# adc-circit-ADS7952.net
KiCad netlist of a schematic drawn in Altium Designer
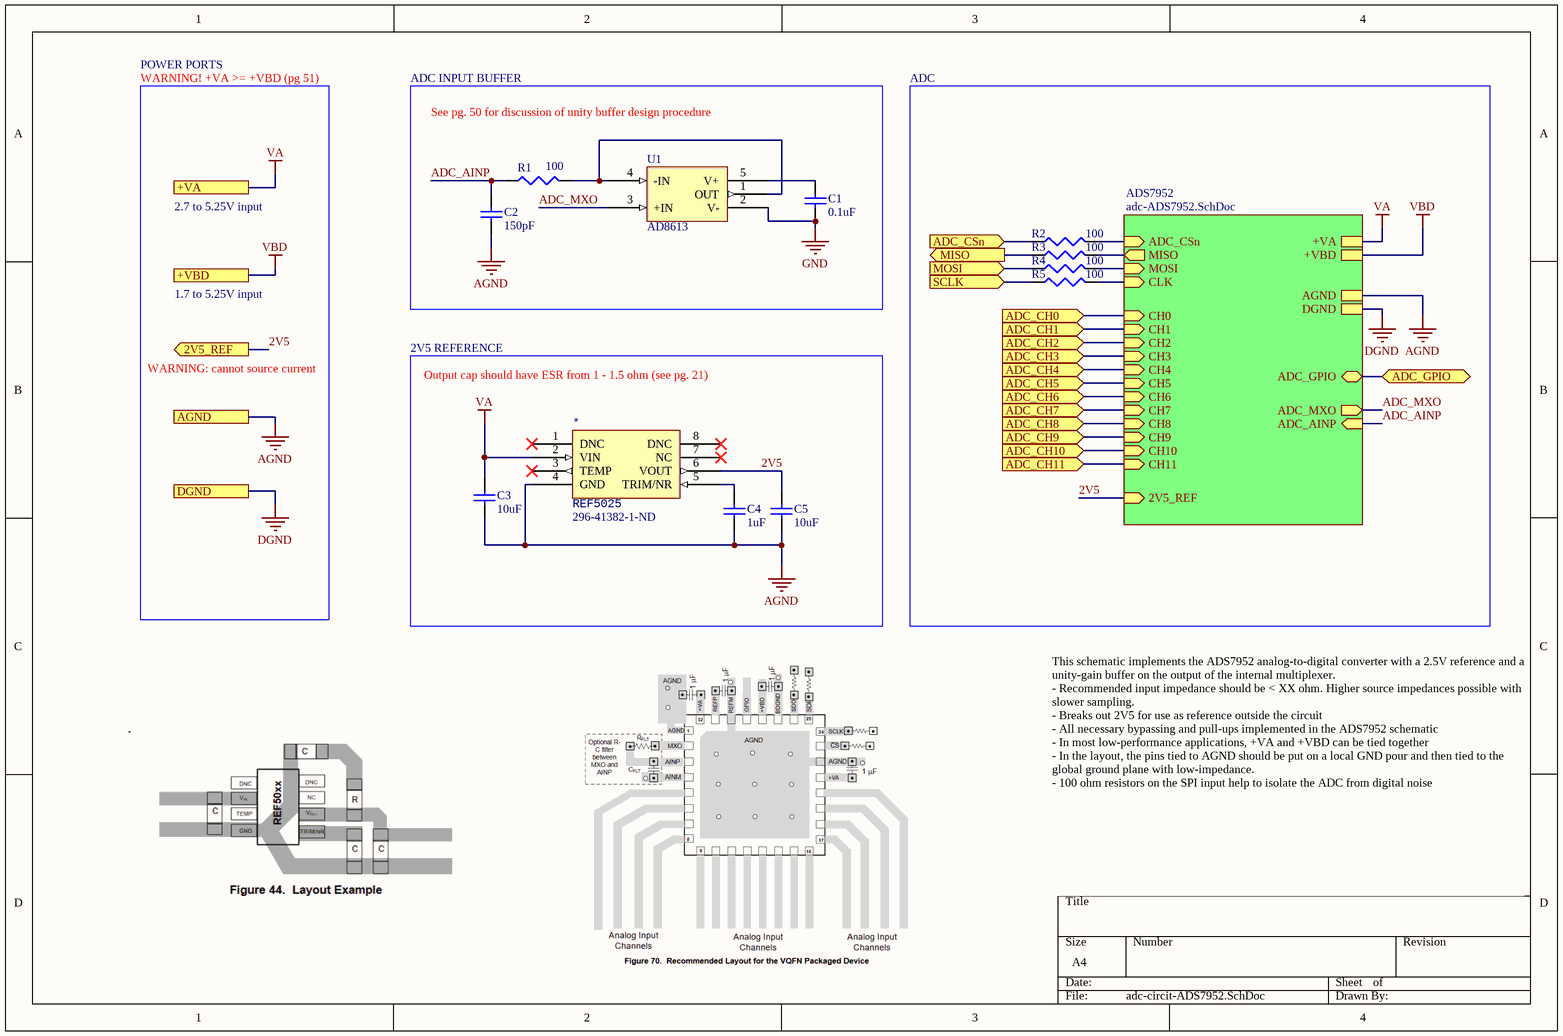
[diagram p0: adc-circit-ADS7952.SchDoc]

(export (version "E")
  (design (tool "Eeschema 10.0.6"))
  (components
    (comp (ref "*")
      (value "REF5025")
      (footprint "SOP65P300X125-8N")
      (description "Voltage Reference")
      (fields (field (name "SUPPLIER PART NUMBER 1") "296-41382-1-ND"))
      (libsource (lib "heron-general") (part "REF5025"))
    )
    (comp (ref "C1")
      (value "0.1uF")
      (footprint "C1206")
      (description "Capacitor (Semiconductor SIM Model)")
      (fields (field (name "PUBLISHER") "Altium Limited"))
      (libsource (lib "Miscellaneous Devices") (part "Cap Semi"))
    )
    (comp (ref "C2")
      (value "150pF")
      (footprint "C1206")
      (description "Capacitor (Semiconductor SIM Model)")
      (fields (field (name "PUBLISHER") "Altium Limited"))
      (libsource (lib "Miscellaneous Devices") (part "Cap Semi"))
    )
    (comp (ref "C3")
      (value "10uF")
      (footprint "RAD-0.3")
      (description "Capacitor")
      (fields (field (name "PUBLISHER") "Altium Limited"))
      (libsource (lib "Miscellaneous Devices") (part "Cap"))
    )
    (comp (ref "C4")
      (value "1uF")
      (footprint "RAD-0.3")
      (description "Capacitor")
      (fields (field (name "PUBLISHER") "Altium Limited"))
      (libsource (lib "Miscellaneous Devices") (part "Cap"))
    )
    (comp (ref "C5")
      (value "10uF")
      (footprint "RAD-0.3")
      (description "ESR between 1-1.5 ohm")
      (fields (field (name "PUBLISHER") "Altium Limited"))
      (libsource (lib "Miscellaneous Devices") (part "Cap"))
    )
    (comp (ref "R1")
      (value "100")
      (footprint "J1-0603")
      (description "Resistor")
      (fields (field (name "PUBLISHER") "Altium Limited"))
      (libsource (lib "Miscellaneous Devices") (part "Res3"))
    )
    (comp (ref "R2")
      (value "100")
      (footprint "J1-0603")
      (description "Resistor")
      (fields (field (name "PUBLISHER") "Altium Limited"))
      (libsource (lib "Miscellaneous Devices") (part "Res3"))
    )
    (comp (ref "R3")
      (value "100")
      (footprint "J1-0603")
      (description "Resistor")
      (fields (field (name "PUBLISHER") "Altium Limited"))
      (libsource (lib "Miscellaneous Devices") (part "Res3"))
    )
    (comp (ref "R4")
      (value "100")
      (footprint "J1-0603")
      (description "Resistor")
      (fields (field (name "PUBLISHER") "Altium Limited"))
      (libsource (lib "Miscellaneous Devices") (part "Res3"))
    )
    (comp (ref "R5")
      (value "100")
      (footprint "J1-0603")
      (description "Resistor")
      (fields (field (name "PUBLISHER") "Altium Limited"))
      (libsource (lib "Miscellaneous Devices") (part "Res3"))
    )
    (comp (ref "U1")
      (value "AD8613")
      (footprint "SOP65P200X125-5N")
      (description "Low power, low noise rail-to-rail op-amp.")
      (libsource (lib "heron-general") (part "AD8613"))
    )
  )
  (nets
    (net (code "1") (name "/2V5") (class "Default")
      (node (ref "*") (pin "6") (pinfunction "VOUT_6") (pintype "output"))
      (node (ref "C5") (pin "2") (pinfunction "2_2") (pintype "passive"))
    )
    (net (code "2") (name "/ADC_AINP") (class "Default")
      (node (ref "C2") (pin "2") (pinfunction "2_2") (pintype "passive"))
      (node (ref "R1") (pin "1") (pinfunction "1_1") (pintype "passive"))
    )
    (net (code "15") (name "/ADC_CSn") (class "Default")
      (node (ref "R2") (pin "1") (pinfunction "1_1") (pintype "passive"))
    )
    (net (code "16") (name "/ADC_CSn_1") (class "Default")
      (node (ref "R2") (pin "2") (pinfunction "2_2") (pintype "passive"))
    )
    (net (code "18") (name "/ADC_MXO") (class "Default")
      (node (ref "U1") (pin "3") (pinfunction "+IN_3") (pintype "input"))
    )
    (net (code "19") (name "/CLK") (class "Default")
      (node (ref "R5") (pin "2") (pinfunction "2_2") (pintype "passive"))
    )
    (net (code "20") (name "/MISO") (class "Default")
      (node (ref "R3") (pin "1") (pinfunction "1_1") (pintype "passive"))
    )
    (net (code "21") (name "/MISO_1") (class "Default")
      (node (ref "R3") (pin "2") (pinfunction "2_2") (pintype "passive"))
    )
    (net (code "22") (name "/MOSI") (class "Default")
      (node (ref "R4") (pin "1") (pinfunction "1_1") (pintype "passive"))
    )
    (net (code "23") (name "/MOSI_1") (class "Default")
      (node (ref "R4") (pin "2") (pinfunction "2_2") (pintype "passive"))
    )
    (net (code "24") (name "/SCLK") (class "Default")
      (node (ref "R5") (pin "1") (pinfunction "1_1") (pintype "passive"))
    )
    (net (code "25") (name "AGND") (class "Default")
      (node (ref "*") (pin "4") (pinfunction "GND_4") (pintype "power_in"))
      (node (ref "C2") (pin "1") (pinfunction "1_1") (pintype "passive"))
      (node (ref "C3") (pin "1") (pinfunction "1_1") (pintype "passive"))
      (node (ref "C4") (pin "1") (pinfunction "1_1") (pintype "passive"))
      (node (ref "C5") (pin "1") (pinfunction "1_1") (pintype "passive"))
    )
    (net (code "27") (name "GND") (class "Default")
      (node (ref "C1") (pin "2") (pinfunction "2_2") (pintype "passive"))
      (node (ref "U1") (pin "2") (pinfunction "V-_2") (pintype "power_in"))
    )
    (net (code "28") (name "Net-(*-TRIM{slash}NR)") (class "Default")
      (node (ref "*") (pin "5") (pinfunction "TRIM/NR_5") (pintype "input"))
      (node (ref "C4") (pin "2") (pinfunction "2_2") (pintype "passive"))
    )
    (net (code "29") (name "Net-(U1--IN)") (class "Default")
      (node (ref "R1") (pin "2") (pinfunction "2_2") (pintype "passive"))
      (node (ref "U1") (pin "1") (pinfunction "OUT_1") (pintype "output"))
      (node (ref "U1") (pin "4") (pinfunction "-IN_4") (pintype "input"))
    )
    (net (code "30") (name "Net-(U1-V+)") (class "Default")
      (node (ref "C1") (pin "1") (pinfunction "1_1") (pintype "passive"))
      (node (ref "U1") (pin "5") (pinfunction "V+_5") (pintype "power_in"))
    )
    (net (code "31") (name "VA") (class "Default")
      (node (ref "*") (pin "2") (pinfunction "VIN_2") (pintype "input"))
      (node (ref "C3") (pin "2") (pinfunction "2_2") (pintype "passive"))
    )
    (net (code "33") (name "unconnected-(*-DNC-Pad1)") (class "Default")
      (node (ref "*") (pin "1") (pinfunction "DNC_1") (pintype "passive+no_connect"))
    )
    (net (code "34") (name "unconnected-(*-DNC-Pad8)") (class "Default")
      (node (ref "*") (pin "8") (pinfunction "DNC_8") (pintype "passive+no_connect"))
    )
    (net (code "35") (name "unconnected-(*-NC-Pad7)") (class "Default")
      (node (ref "*") (pin "7") (pinfunction "NC_7") (pintype "passive+no_connect"))
    )
    (net (code "36") (name "unconnected-(*-TEMP-Pad3)") (class "Default")
      (node (ref "*") (pin "3") (pinfunction "TEMP_3") (pintype "output+no_connect"))
    )
  )
)
